# power_filter.net
KiCad netlist of a schematic drawn in Altium Designer
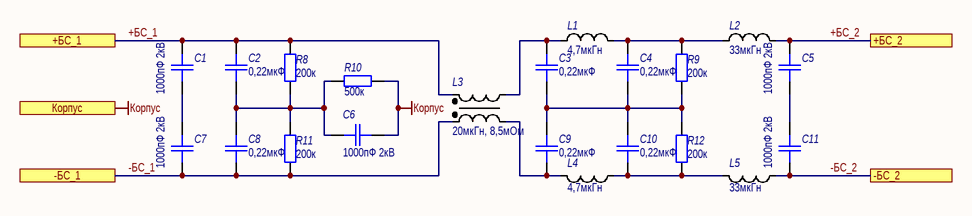
[diagram p0: power_filter.SchDoc]

(export (version "E")
  (design (tool "Eeschema 10.0.6"))
  (components
    (comp (ref "C1")
      (value "1000пФ 2кВ")
      (footprint "SMD_1206")
      (description "Capacitor")
      (libsource (lib "Passive") (part "Capacitor"))
    )
    (comp (ref "C2")
      (value "0,22мкФ")
      (footprint "SMD_0805")
      (description "Capacitor")
      (libsource (lib "Passive") (part "Capacitor"))
    )
    (comp (ref "C3")
      (value "0,22мкФ")
      (footprint "SMD_0805")
      (description "Capacitor")
      (libsource (lib "Passive") (part "Capacitor"))
    )
    (comp (ref "C4")
      (value "0,22мкФ")
      (footprint "SMD_0805")
      (description "Capacitor")
      (libsource (lib "Passive") (part "Capacitor"))
    )
    (comp (ref "C5")
      (value "1000пФ 2кВ")
      (footprint "SMD_1206")
      (description "Capacitor")
      (libsource (lib "Passive") (part "Capacitor"))
    )
    (comp (ref "C6")
      (value "1000пФ 2кВ")
      (footprint "SMD_1206")
      (description "Capacitor")
      (libsource (lib "Passive") (part "Capacitor"))
    )
    (comp (ref "C7")
      (value "1000пФ 2кВ")
      (footprint "SMD_1206")
      (description "Capacitor")
      (libsource (lib "Passive") (part "Capacitor"))
    )
    (comp (ref "C8")
      (value "0,22мкФ")
      (footprint "SMD_0805")
      (description "Capacitor")
      (libsource (lib "Passive") (part "Capacitor"))
    )
    (comp (ref "C9")
      (value "0,22мкФ")
      (footprint "SMD_0805")
      (description "Capacitor")
      (libsource (lib "Passive") (part "Capacitor"))
    )
    (comp (ref "C10")
      (value "0,22мкФ")
      (footprint "SMD_0805")
      (description "Capacitor")
      (libsource (lib "Passive") (part "Capacitor"))
    )
    (comp (ref "C11")
      (value "1000пФ 2кВ")
      (footprint "SMD_1206")
      (description "Capacitor")
      (libsource (lib "Passive") (part "Capacitor"))
    )
    (comp (ref "L1")
      (value "4,7мкГн")
      (footprint "SMD_0805")
      (description "Inductor")
      (libsource (lib "Passive") (part "Inductor"))
    )
    (comp (ref "L2")
      (value "33мкГн")
      (footprint "SMD_size_B")
      (description "Inductor")
      (libsource (lib "Passive") (part "Inductor"))
    )
    (comp (ref "L3")
      (value "20мкГн, 8,5мОм")
      (footprint "PLT10HH")
      (description "Coupled inductor")
      (libsource (lib "Passive") (part "Inductor_coupled"))
    )
    (comp (ref "L4")
      (value "4,7мкГн")
      (footprint "SMD_0805")
      (description "Inductor")
      (libsource (lib "Passive") (part "Inductor"))
    )
    (comp (ref "L5")
      (value "33мкГн")
      (footprint "SMD_size_B")
      (description "Inductor")
      (libsource (lib "Passive") (part "Inductor"))
    )
    (comp (ref "R8")
      (value "200к")
      (footprint "SMD_0805")
      (description "Resistor")
      (libsource (lib "Passive") (part "Resistor"))
    )
    (comp (ref "R9")
      (value "200к")
      (footprint "SMD_0805")
      (description "Resistor")
      (libsource (lib "Passive") (part "Resistor"))
    )
    (comp (ref "R10")
      (value "500к")
      (footprint "SMD_0805")
      (description "Resistor")
      (libsource (lib "") (part "Resistor_1"))
    )
    (comp (ref "R11")
      (value "200к")
      (footprint "SMD_0805")
      (description "Resistor")
      (libsource (lib "Passive") (part "Resistor"))
    )
    (comp (ref "R12")
      (value "200к")
      (footprint "SMD_0805")
      (description "Resistor")
      (libsource (lib "Passive") (part "Resistor"))
    )
  )
  (nets
    (net (code "1") (name "/+БС_1") (class "Default")
      (node (ref "C1") (pin "1") (pinfunction "1_1") (pintype "passive"))
      (node (ref "C2") (pin "2") (pinfunction "2_2") (pintype "passive"))
      (node (ref "L3") (pin "3") (pinfunction "3_3") (pintype "passive"))
      (node (ref "R8") (pin "2") (pinfunction "2_2") (pintype "passive"))
    )
    (net (code "2") (name "/+БС_2") (class "Default")
      (node (ref "C5") (pin "1") (pinfunction "1_1") (pintype "passive"))
      (node (ref "L2") (pin "2") (pinfunction "2_2") (pintype "passive"))
    )
    (net (code "3") (name "/-БС_1") (class "Default")
      (node (ref "C7") (pin "2") (pinfunction "2_2") (pintype "passive"))
      (node (ref "C8") (pin "1") (pinfunction "1_1") (pintype "passive"))
      (node (ref "L3") (pin "2") (pinfunction "2_2") (pintype "passive"))
      (node (ref "R11") (pin "1") (pinfunction "1_1") (pintype "passive"))
    )
    (net (code "4") (name "/-БС_2") (class "Default")
      (node (ref "C11") (pin "2") (pinfunction "2_2") (pintype "passive"))
      (node (ref "L5") (pin "1") (pinfunction "1_1") (pintype "passive"))
    )
    (net (code "5") (name "Net-(C1-Pad2)") (class "Default")
      (node (ref "C1") (pin "2") (pinfunction "2_2") (pintype "passive"))
      (node (ref "C7") (pin "1") (pinfunction "1_1") (pintype "passive"))
    )
    (net (code "6") (name "Net-(C2-Pad1)") (class "Default")
      (node (ref "C2") (pin "1") (pinfunction "1_1") (pintype "passive"))
      (node (ref "C6") (pin "2") (pinfunction "2_2") (pintype "passive"))
      (node (ref "C8") (pin "2") (pinfunction "2_2") (pintype "passive"))
      (node (ref "R10") (pin "1") (pinfunction "1_1") (pintype "passive"))
      (node (ref "R11") (pin "2") (pinfunction "2_2") (pintype "passive"))
      (node (ref "R8") (pin "1") (pinfunction "1_1") (pintype "passive"))
    )
    (net (code "7") (name "Net-(C3-Pad2)") (class "Default")
      (node (ref "C3") (pin "2") (pinfunction "2_2") (pintype "passive"))
      (node (ref "L1") (pin "1") (pinfunction "1_1") (pintype "passive"))
      (node (ref "L3") (pin "4") (pinfunction "4_4") (pintype "passive"))
    )
    (net (code "8") (name "Net-(C4-Pad2)") (class "Default")
      (node (ref "C4") (pin "2") (pinfunction "2_2") (pintype "passive"))
      (node (ref "L1") (pin "2") (pinfunction "2_2") (pintype "passive"))
      (node (ref "L2") (pin "1") (pinfunction "1_1") (pintype "passive"))
      (node (ref "R9") (pin "2") (pinfunction "2_2") (pintype "passive"))
    )
    (net (code "9") (name "Net-(C9-Pad1)") (class "Default")
      (node (ref "C9") (pin "1") (pinfunction "1_1") (pintype "passive"))
      (node (ref "L3") (pin "1") (pinfunction "1_1") (pintype "passive"))
      (node (ref "L4") (pin "2") (pinfunction "2_2") (pintype "passive"))
    )
    (net (code "10") (name "Net-(C10-Pad1)") (class "Default")
      (node (ref "C10") (pin "1") (pinfunction "1_1") (pintype "passive"))
      (node (ref "L4") (pin "1") (pinfunction "1_1") (pintype "passive"))
      (node (ref "L5") (pin "2") (pinfunction "2_2") (pintype "passive"))
      (node (ref "R12") (pin "1") (pinfunction "1_1") (pintype "passive"))
    )
    (net (code "11") (name "Net-(C10-Pad2)") (class "Default")
      (node (ref "C10") (pin "2") (pinfunction "2_2") (pintype "passive"))
      (node (ref "C3") (pin "1") (pinfunction "1_1") (pintype "passive"))
      (node (ref "C4") (pin "1") (pinfunction "1_1") (pintype "passive"))
      (node (ref "C9") (pin "2") (pinfunction "2_2") (pintype "passive"))
      (node (ref "R12") (pin "2") (pinfunction "2_2") (pintype "passive"))
      (node (ref "R9") (pin "1") (pinfunction "1_1") (pintype "passive"))
    )
    (net (code "12") (name "Net-(C11-Pad1)") (class "Default")
      (node (ref "C11") (pin "1") (pinfunction "1_1") (pintype "passive"))
      (node (ref "C5") (pin "2") (pinfunction "2_2") (pintype "passive"))
    )
    (net (code "13") (name "Корпус") (class "Default")
      (node (ref "C6") (pin "1") (pinfunction "1_1") (pintype "passive"))
      (node (ref "R10") (pin "2") (pinfunction "2_2") (pintype "passive"))
    )
  )
)
